# p2c-001.net
KiCad netlist of a schematic drawn in EAGLE
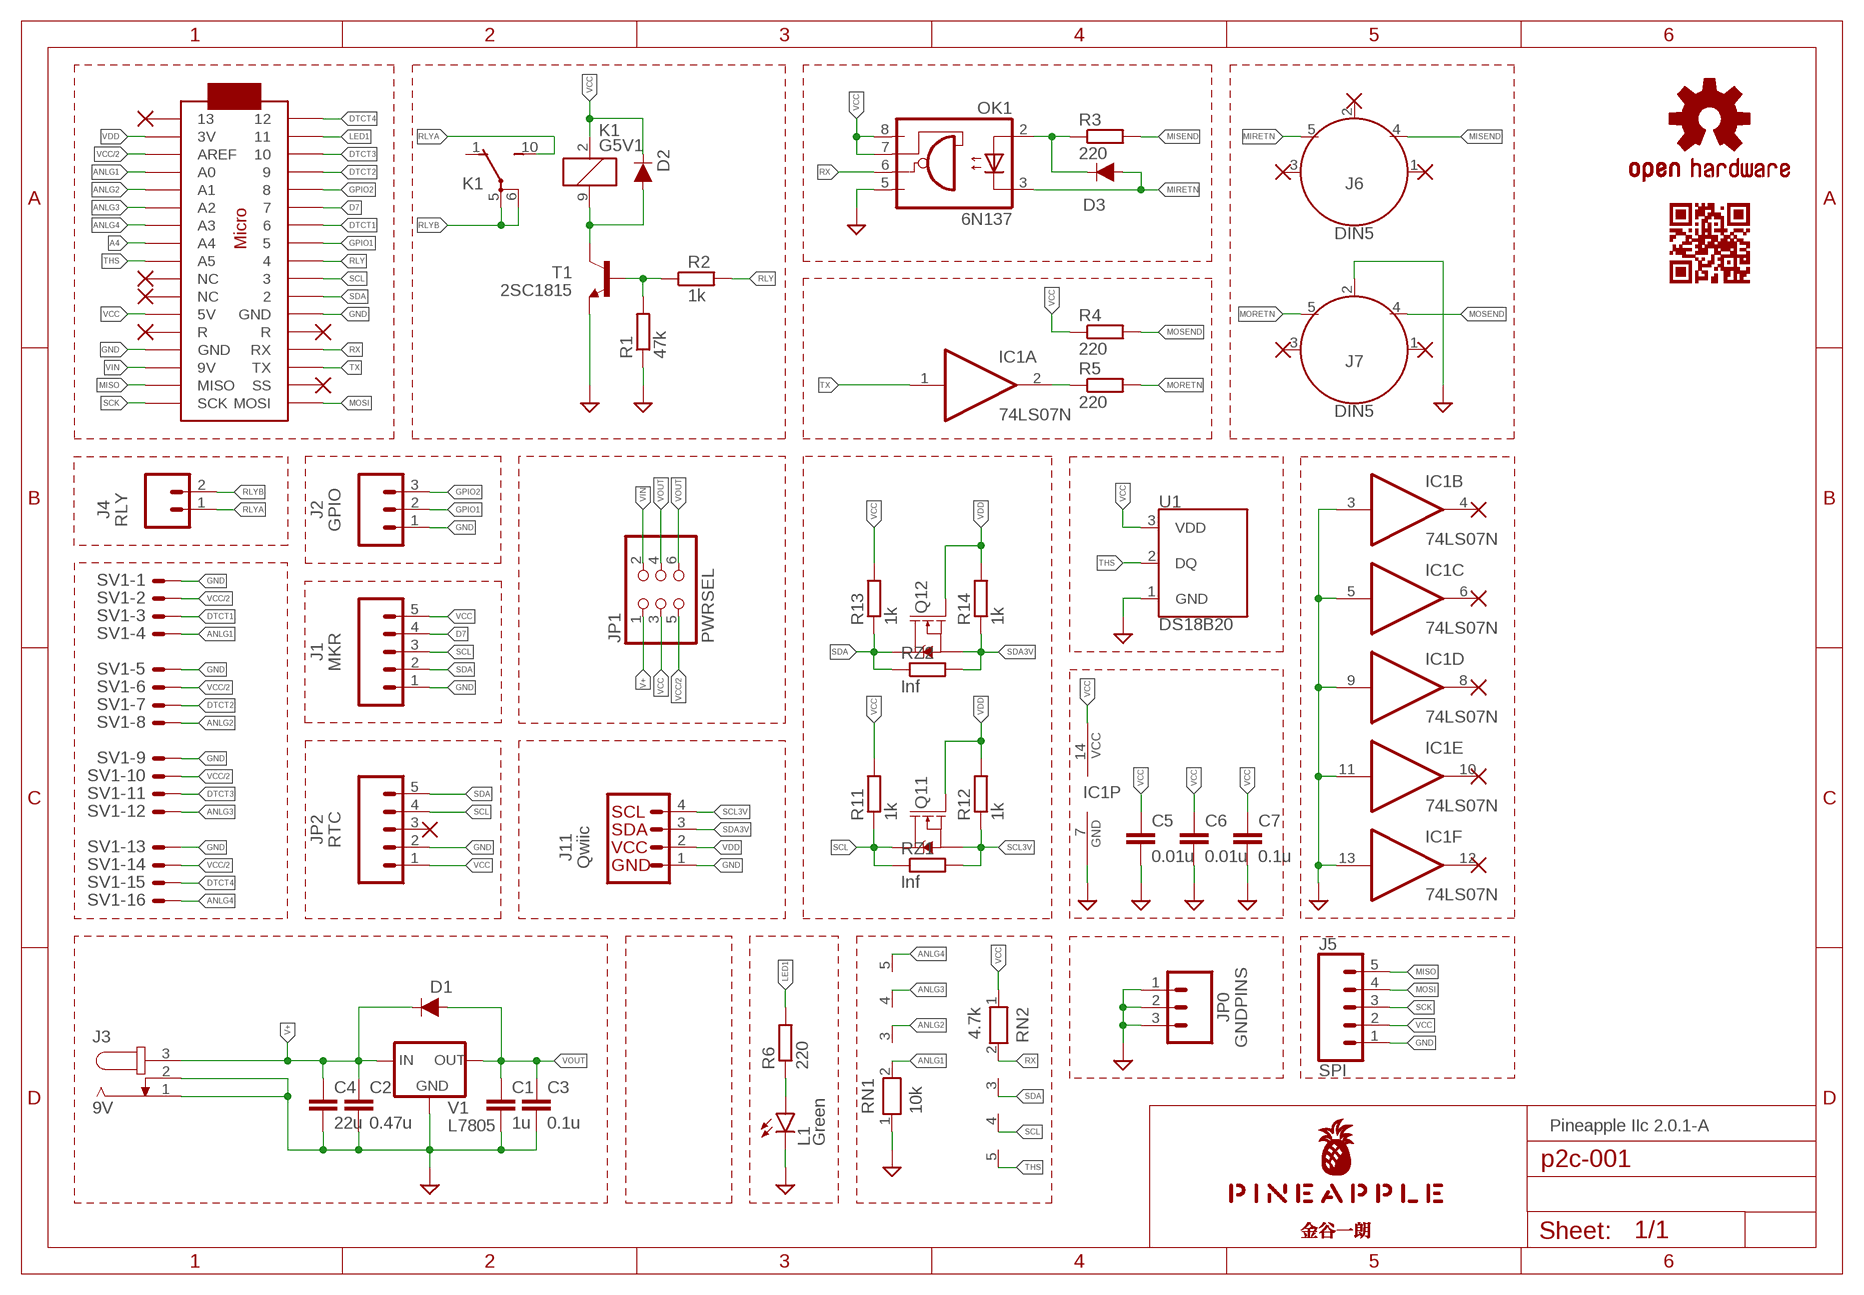
[diagram p0: schematic, sheet 1]

(export (version "E")
  (design (tool "Eeschema 10.0.6"))
  (components
    (comp (ref "C1")
      (value "1u")
      (footprint "eagle-import:C050-024X044")
      (libsource (lib "eagle-import") (part "C-EU050-024X044"))
    )
    (comp (ref "C2")
      (value "0.47u")
      (footprint "eagle-import:C050-024X044")
      (libsource (lib "eagle-import") (part "C-EU050-024X044"))
    )
    (comp (ref "C3")
      (value "0.1u")
      (footprint "eagle-import:C025-024X044")
      (libsource (lib "eagle-import") (part "C-EU025-024X044"))
    )
    (comp (ref "C4")
      (value "22u")
      (footprint "eagle-import:C025-050X050")
      (libsource (lib "eagle-import") (part "C-EU025-050X050"))
    )
    (comp (ref "C5")
      (value "0.01u")
      (footprint "eagle-import:C025-024X044")
      (libsource (lib "eagle-import") (part "resistor_348_C-EU025-024X044"))
    )
    (comp (ref "C6")
      (value "0.01u")
      (footprint "eagle-import:C025-024X044")
      (libsource (lib "eagle-import") (part "resistor_348_C-EU025-024X044"))
    )
    (comp (ref "C7")
      (value "0.1u")
      (footprint "eagle-import:C025-024X044")
      (libsource (lib "eagle-import") (part "C-EU025-024X044"))
    )
    (comp (ref "D1")
      (value "DIODE-1N4148")
      (footprint "eagle-import:DIODE-1N4148")
      (libsource (lib "eagle-import") (part "DIODE-1N4148"))
    )
    (comp (ref "D2")
      (value "DIODE-1N4148")
      (footprint "eagle-import:DIODE-1N4148")
      (libsource (lib "eagle-import") (part "DIODE-1N4148"))
    )
    (comp (ref "D3")
      (value "DIODE-1N4148")
      (footprint "eagle-import:DIODE-1N4148")
      (libsource (lib "eagle-import") (part "DIODE-1N4148"))
    )
    (comp (ref "IC1")
      (value "74LS07N")
      (footprint "eagle-import:DIL14")
      (libsource (lib "eagle-import") (part "7407NLS"))
    )
    (comp (ref "J1")
      (value "MKR")
      (footprint "eagle-import:JST-5-PTH")
      (libsource (lib "eagle-import") (part "CONN_05JST"))
    )
    (comp (ref "J2")
      (value "GPIO")
      (footprint "eagle-import:JST-3-PTH")
      (libsource (lib "eagle-import") (part "CONN_03JST-PTH"))
    )
    (comp (ref "J3")
      (value "9V")
      (footprint "eagle-import:SPC4077")
      (libsource (lib "eagle-import") (part "JACK-PLUG0"))
    )
    (comp (ref "J4")
      (value "RLY")
      (footprint "eagle-import:JST-2-PTH")
      (libsource (lib "eagle-import") (part "CONN_02JST-PTH-2"))
    )
    (comp (ref "J5")
      (value "SPI")
      (footprint "eagle-import:JST-5-PTH-VERT")
      (libsource (lib "eagle-import") (part "CONN_05JST-VERT"))
    )
    (comp (ref "J6")
      (value "DIN5")
      (footprint "eagle-import:DIN5-RA-PTH")
      (libsource (lib "eagle-import") (part "DIN5"))
    )
    (comp (ref "J7")
      (value "DIN5")
      (footprint "eagle-import:DIN5-RA-PTH")
      (libsource (lib "eagle-import") (part "DIN5"))
    )
    (comp (ref "J11")
      (value "Qwiic")
      (footprint "eagle-import:1X04_1MM_RA")
      (libsource (lib "eagle-import") (part "QWIIC_CONNECTORJS-1MM"))
    )
    (comp (ref "JP0")
      (value "GNDPINS")
      (footprint "eagle-import:1X03")
      (libsource (lib "eagle-import") (part "CONN_03"))
    )
    (comp (ref "JP1")
      (value "PWRSEL")
      (footprint "eagle-import:2X03")
      (libsource (lib "eagle-import") (part "PINHD-2X3"))
    )
    (comp (ref "JP2")
      (value "RTC")
      (footprint "eagle-import:1X05")
      (libsource (lib "eagle-import") (part "CONN_05"))
    )
    (comp (ref "K1")
      (value "G5V1")
      (footprint "eagle-import:G5V1")
      (fields (field (name "MPN") "G5V-1-DC24"))
      (libsource (lib "eagle-import") (part "G5V1"))
    )
    (comp (ref "L1")
      (value "Green")
      (footprint "eagle-import:LED3MM")
      (libsource (lib "eagle-import") (part "LED3MM"))
    )
    (comp (ref "LOGO1")
      (value "OSHW-LOGOS-COPPER")
      (footprint "eagle-import:OSHW-LOGO-S_COPPER")
      (libsource (lib "eagle-import") (part "OSHW-LOGOS-COPPER"))
    )
    (comp (ref "OK1")
      (value "6N137")
      (footprint "eagle-import:DIL08")
      (libsource (lib "eagle-import") (part "6N137"))
    )
    (comp (ref "Q11")
      (value "220mA/50V/3.5Ω")
      (footprint "eagle-import:SOT23-3")
      (libsource (lib "eagle-import") (part "MOSFET-NCH-BSS138"))
    )
    (comp (ref "Q12")
      (value "220mA/50V/3.5Ω")
      (footprint "eagle-import:SOT23-3")
      (libsource (lib "eagle-import") (part "MOSFET-NCH-BSS138"))
    )
    (comp (ref "R1")
      (value "47k")
      (footprint "eagle-import:0204_5")
      (libsource (lib "eagle-import") (part "R-EU_0204/5"))
    )
    (comp (ref "R2")
      (value "1k")
      (footprint "eagle-import:0204_5")
      (libsource (lib "eagle-import") (part "R-EU_0204/5"))
    )
    (comp (ref "R3")
      (value "220")
      (footprint "eagle-import:0204_5")
      (libsource (lib "eagle-import") (part "R-EU_0204/5"))
    )
    (comp (ref "R4")
      (value "220")
      (footprint "eagle-import:0204_5")
      (libsource (lib "eagle-import") (part "R-EU_0204/5"))
    )
    (comp (ref "R5")
      (value "220")
      (footprint "eagle-import:0204_5")
      (libsource (lib "eagle-import") (part "R-EU_0204/5"))
    )
    (comp (ref "R6")
      (value "220")
      (footprint "eagle-import:0204_5")
      (libsource (lib "eagle-import") (part "R-EU_0204/5"))
    )
    (comp (ref "R11")
      (value "1k")
      (footprint "eagle-import:R2012")
      (libsource (lib "eagle-import") (part "R-EU_R2012"))
    )
    (comp (ref "R12")
      (value "1k")
      (footprint "eagle-import:R2012")
      (libsource (lib "eagle-import") (part "R-EU_R2012"))
    )
    (comp (ref "R13")
      (value "1k")
      (footprint "eagle-import:R2012")
      (libsource (lib "eagle-import") (part "R-EU_R2012"))
    )
    (comp (ref "R14")
      (value "1k")
      (footprint "eagle-import:R2012")
      (libsource (lib "eagle-import") (part "R-EU_R2012"))
    )
    (comp (ref "RN1")
      (value "10k")
      (footprint "eagle-import:RN-5")
      (libsource (lib "eagle-import") (part "RN04"))
    )
    (comp (ref "RN2")
      (value "4.7k")
      (footprint "eagle-import:RN-5")
      (libsource (lib "eagle-import") (part "RN04"))
    )
    (comp (ref "RZ1")
      (value "Inf")
      (footprint "eagle-import:R2012")
      (libsource (lib "eagle-import") (part "R-EU_R2012"))
    )
    (comp (ref "RZ2")
      (value "Inf")
      (footprint "eagle-import:R2012")
      (libsource (lib "eagle-import") (part "R-EU_R2012"))
    )
    (comp (ref "SV1")
      (value "ML16LE")
      (footprint "eagle-import:ML16L")
      (libsource (lib "eagle-import") (part "ML16LE"))
    )
    (comp (ref "T1")
      (value "2SC1815")
      (footprint "eagle-import:TO92-ECB")
      (libsource (lib "eagle-import") (part "2SC1815"))
    )
    (comp (ref "U$1")
      (value "PINEAPPLE450_SILK")
      (footprint "eagle-import:PINEAPPLE450_SILK")
      (libsource (lib "eagle-import") (part "PINEAPPLE450_SILK"))
    )
    (comp (ref "U$2")
      (value "ARDUINOMICRO")
      (footprint "eagle-import:ARDUINOMICRO")
      (libsource (lib "eagle-import") (part "ARDUINOMICRO"))
    )
    (comp (ref "U$3")
      (value "KANAYA768_SILK")
      (footprint "eagle-import:KANAYA768_SILK")
      (libsource (lib "eagle-import") (part "KANAYA768_SILK"))
    )
    (comp (ref "U$4")
      (value "CARDQRCODE450_SILK")
      (footprint "eagle-import:CARDQRCODE450_SILK")
      (libsource (lib "eagle-import") (part "CARDQRCODE450_SILK"))
    )
    (comp (ref "U1")
      (value "DS18B20")
      (footprint "eagle-import:TO-92-AMMO")
      (libsource (lib "eagle-import") (part "DS18B20"))
    )
    (comp (ref "V1")
      (value "L7805")
      (footprint "eagle-import:78XXS")
      (libsource (lib "eagle-import") (part "78XXS"))
    )
  )
  (nets
    (net (code "1") (name "A4") (class "Default")
      (node (ref "U$2") (pin "P$27") (pinfunction "A4_P$27") (pintype "bidirectional"))
    )
    (net (code "2") (name "ANLG1") (class "Default")
      (node (ref "RN1") (pin "2") (pinfunction "2_2") (pintype "passive"))
      (node (ref "SV1") (pin "4") (pinfunction "S_4") (pintype "passive"))
      (node (ref "U$2") (pin "P$31") (pinfunction "A0_P$31") (pintype "bidirectional"))
    )
    (net (code "3") (name "ANLG2") (class "Default")
      (node (ref "RN1") (pin "3") (pinfunction "3_3") (pintype "passive"))
      (node (ref "SV1") (pin "8") (pinfunction "S_8") (pintype "passive"))
      (node (ref "U$2") (pin "P$30") (pinfunction "A1_P$30") (pintype "bidirectional"))
    )
    (net (code "4") (name "ANLG3") (class "Default")
      (node (ref "RN1") (pin "4") (pinfunction "4_4") (pintype "passive"))
      (node (ref "SV1") (pin "12") (pinfunction "S_12") (pintype "passive"))
      (node (ref "U$2") (pin "P$29") (pinfunction "A2_P$29") (pintype "bidirectional"))
    )
    (net (code "5") (name "ANLG4") (class "Default")
      (node (ref "RN1") (pin "5") (pinfunction "5_5") (pintype "passive"))
      (node (ref "SV1") (pin "16") (pinfunction "S_16") (pintype "passive"))
      (node (ref "U$2") (pin "P$28") (pinfunction "A3_P$28") (pintype "bidirectional"))
    )
    (net (code "6") (name "D7") (class "Default")
      (node (ref "J1") (pin "4") (pinfunction "4_4") (pintype "passive"))
      (node (ref "U$2") (pin "P$6") (pinfunction "7_P$6") (pintype "bidirectional"))
    )
    (net (code "7") (name "DTCT1") (class "Default")
      (node (ref "SV1") (pin "3") (pinfunction "S_3") (pintype "passive"))
      (node (ref "U$2") (pin "P$7") (pinfunction "6_P$7") (pintype "bidirectional"))
    )
    (net (code "8") (name "DTCT2") (class "Default")
      (node (ref "SV1") (pin "7") (pinfunction "S_7") (pintype "passive"))
      (node (ref "U$2") (pin "P$4") (pinfunction "9_P$4") (pintype "bidirectional"))
    )
    (net (code "9") (name "DTCT3") (class "Default")
      (node (ref "SV1") (pin "11") (pinfunction "S_11") (pintype "passive"))
      (node (ref "U$2") (pin "P$3") (pinfunction "10_P$3") (pintype "bidirectional"))
    )
    (net (code "10") (name "DTCT4") (class "Default")
      (node (ref "SV1") (pin "15") (pinfunction "S_15") (pintype "passive"))
      (node (ref "U$2") (pin "P$1") (pinfunction "12_P$1") (pintype "bidirectional"))
    )
    (net (code "11") (name "GND") (class "Default")
      (node (ref "C1") (pin "2") (pinfunction "2_2") (pintype "passive"))
      (node (ref "C2") (pin "2") (pinfunction "2_2") (pintype "passive"))
      (node (ref "C3") (pin "2") (pinfunction "2_2") (pintype "passive"))
      (node (ref "C4") (pin "2") (pinfunction "2_2") (pintype "passive"))
      (node (ref "C5") (pin "2") (pinfunction "2_2") (pintype "passive"))
      (node (ref "C6") (pin "2") (pinfunction "2_2") (pintype "passive"))
      (node (ref "C7") (pin "2") (pinfunction "2_2") (pintype "passive"))
      (node (ref "IC1") (pin "11") (pinfunction "I_11") (pintype "input"))
      (node (ref "IC1") (pin "13") (pinfunction "I_13") (pintype "input"))
      (node (ref "IC1") (pin "3") (pinfunction "I_3") (pintype "input"))
      (node (ref "IC1") (pin "5") (pinfunction "I_5") (pintype "input"))
      (node (ref "IC1") (pin "7") (pinfunction "GND_7") (pintype "power_in"))
      (node (ref "IC1") (pin "9") (pinfunction "I_9") (pintype "input"))
      (node (ref "J1") (pin "1") (pinfunction "1_1") (pintype "passive"))
      (node (ref "J11") (pin "1") (pinfunction "GND_1") (pintype "power_in"))
      (node (ref "J2") (pin "1") (pinfunction "1_1") (pintype "passive"))
      (node (ref "J3") (pin "1") (pinfunction "1_1") (pintype "passive"))
      (node (ref "J3") (pin "2") (pinfunction "2_2") (pintype "passive"))
      (node (ref "J5") (pin "1") (pinfunction "1_1") (pintype "passive"))
      (node (ref "J7") (pin "2") (pinfunction "2_2") (pintype "bidirectional"))
      (node (ref "JP0") (pin "1") (pinfunction "1_1") (pintype "passive"))
      (node (ref "JP0") (pin "2") (pinfunction "2_2") (pintype "passive"))
      (node (ref "JP0") (pin "3") (pinfunction "3_3") (pintype "passive"))
      (node (ref "JP2") (pin "2") (pinfunction "2_2") (pintype "passive"))
      (node (ref "L1") (pin "K") (pinfunction "C_K") (pintype "passive"))
      (node (ref "OK1") (pin "5") (pinfunction "GND_5") (pintype "passive"))
      (node (ref "R1") (pin "1") (pinfunction "1_1") (pintype "passive"))
      (node (ref "RN1") (pin "1") (pinfunction "1_1") (pintype "passive"))
      (node (ref "SV1") (pin "1") (pinfunction "S_1") (pintype "passive"))
      (node (ref "SV1") (pin "13") (pinfunction "S_13") (pintype "passive"))
      (node (ref "SV1") (pin "5") (pinfunction "S_5") (pintype "passive"))
      (node (ref "SV1") (pin "9") (pinfunction "S_9") (pintype "passive"))
      (node (ref "T1") (pin "E") (pinfunction "E_E") (pintype "passive"))
      (node (ref "U$2") (pin "P$12") (pinfunction "GND_P$12") (pintype "bidirectional"))
      (node (ref "U$2") (pin "P$21") (pinfunction "GND_P$21") (pintype "bidirectional"))
      (node (ref "U1") (pin "1") (pinfunction "GND_1") (pintype "power_in"))
      (node (ref "V1") (pin "GND") (pinfunction "GND_GND") (pintype "input"))
    )
    (net (code "12") (name "GPIO1") (class "Default")
      (node (ref "J2") (pin "2") (pinfunction "2_2") (pintype "passive"))
      (node (ref "U$2") (pin "P$8") (pinfunction "5_P$8") (pintype "bidirectional"))
    )
    (net (code "13") (name "GPIO2") (class "Default")
      (node (ref "J2") (pin "3") (pinfunction "3_3") (pintype "passive"))
      (node (ref "U$2") (pin "P$5") (pinfunction "8_P$5") (pintype "bidirectional"))
    )
    (net (code "14") (name "LED1") (class "Default")
      (node (ref "R6") (pin "2") (pinfunction "2_2") (pintype "passive"))
      (node (ref "U$2") (pin "P$2") (pinfunction "11_P$2") (pintype "bidirectional"))
    )
    (net (code "15") (name "MIRETN") (class "Default")
      (node (ref "D3") (pin "A") (pinfunction "A_A") (pintype "passive"))
      (node (ref "J6") (pin "5") (pinfunction "5_5") (pintype "bidirectional"))
      (node (ref "OK1") (pin "3") (pinfunction "C_3") (pintype "passive"))
    )
    (net (code "16") (name "MISEND") (class "Default")
      (node (ref "J6") (pin "4") (pinfunction "4_4") (pintype "bidirectional"))
      (node (ref "R3") (pin "2") (pinfunction "2_2") (pintype "passive"))
    )
    (net (code "17") (name "MISO") (class "Default")
      (node (ref "J5") (pin "5") (pinfunction "5_5") (pintype "passive"))
      (node (ref "U$2") (pin "P$19") (pinfunction "MISO_P$19") (pintype "bidirectional"))
    )
    (net (code "18") (name "MORETN") (class "Default")
      (node (ref "J7") (pin "5") (pinfunction "5_5") (pintype "bidirectional"))
      (node (ref "R5") (pin "2") (pinfunction "2_2") (pintype "passive"))
    )
    (net (code "19") (name "MOSEND") (class "Default")
      (node (ref "J7") (pin "4") (pinfunction "4_4") (pintype "bidirectional"))
      (node (ref "R4") (pin "2") (pinfunction "2_2") (pintype "passive"))
    )
    (net (code "20") (name "MOSI") (class "Default")
      (node (ref "J5") (pin "4") (pinfunction "4_4") (pintype "passive"))
      (node (ref "U$2") (pin "P$17") (pinfunction "MOSI_P$17") (pintype "bidirectional"))
    )
    (net (code "21") (name "Net-(IC1A-O)") (class "Default")
      (node (ref "IC1") (pin "2") (pinfunction "O_2") (pintype "open_collector"))
      (node (ref "R5") (pin "1") (pinfunction "1_1") (pintype "passive"))
    )
    (net (code "22") (name "Net-(K1A-2)") (class "Default")
      (node (ref "D2") (pin "A") (pinfunction "A_A") (pintype "passive"))
      (node (ref "K1") (pin "9") (pinfunction "2_9") (pintype "passive"))
      (node (ref "T1") (pin "C") (pinfunction "C_C") (pintype "passive"))
    )
    (net (code "23") (name "Net-(L1-PadA)") (class "Default")
      (node (ref "L1") (pin "A") (pinfunction "A_A") (pintype "passive"))
      (node (ref "R6") (pin "1") (pinfunction "1_1") (pintype "passive"))
    )
    (net (code "24") (name "Net-(OK1-A)") (class "Default")
      (node (ref "D3") (pin "C") (pinfunction "C_C") (pintype "passive"))
      (node (ref "OK1") (pin "2") (pinfunction "A_2") (pintype "passive"))
      (node (ref "R3") (pin "1") (pinfunction "1_1") (pintype "passive"))
    )
    (net (code "25") (name "Net-(R1-Pad2)") (class "Default")
      (node (ref "R1") (pin "2") (pinfunction "2_2") (pintype "passive"))
      (node (ref "R2") (pin "1") (pinfunction "1_1") (pintype "passive"))
      (node (ref "T1") (pin "B") (pinfunction "B_B") (pintype "passive"))
    )
    (net (code "26") (name "RLY") (class "Default")
      (node (ref "R2") (pin "2") (pinfunction "2_2") (pintype "passive"))
      (node (ref "U$2") (pin "P$9") (pinfunction "4_P$9") (pintype "bidirectional"))
    )
    (net (code "27") (name "RLYA") (class "Default")
      (node (ref "J4") (pin "1") (pinfunction "1_1") (pintype "passive"))
      (node (ref "K1") (pin "10") (pinfunction "S_10") (pintype "passive"))
    )
    (net (code "28") (name "RLYB") (class "Default")
      (node (ref "J4") (pin "2") (pinfunction "2_2") (pintype "passive"))
      (node (ref "K1") (pin "5") (pinfunction "P_5") (pintype "passive"))
      (node (ref "K1") (pin "6") (pinfunction "P_6") (pintype "passive"))
    )
    (net (code "29") (name "RX") (class "Default")
      (node (ref "OK1") (pin "6") (pinfunction "VO_6") (pintype "passive"))
      (node (ref "RN2") (pin "2") (pinfunction "2_2") (pintype "passive"))
      (node (ref "U$2") (pin "P$14") (pinfunction "RX_P$14") (pintype "bidirectional"))
    )
    (net (code "30") (name "SCK") (class "Default")
      (node (ref "J5") (pin "3") (pinfunction "3_3") (pintype "passive"))
      (node (ref "U$2") (pin "P$18") (pinfunction "SCK_P$18") (pintype "bidirectional"))
    )
    (net (code "31") (name "SCL") (class "Default")
      (node (ref "J1") (pin "3") (pinfunction "3_3") (pintype "passive"))
      (node (ref "JP2") (pin "4") (pinfunction "4_4") (pintype "passive"))
      (node (ref "Q11") (pin "3") (pinfunction "D_3") (pintype "bidirectional"))
      (node (ref "R11") (pin "1") (pinfunction "1_1") (pintype "passive"))
      (node (ref "RN2") (pin "4") (pinfunction "4_4") (pintype "passive"))
      (node (ref "RZ1") (pin "1") (pinfunction "1_1") (pintype "passive"))
      (node (ref "U$2") (pin "P$10") (pinfunction "3_P$10") (pintype "bidirectional"))
    )
    (net (code "32") (name "SCL3V") (class "Default")
      (node (ref "J11") (pin "4") (pinfunction "SCL_4") (pintype "passive"))
      (node (ref "Q11") (pin "2") (pinfunction "S_2") (pintype "bidirectional"))
      (node (ref "R12") (pin "1") (pinfunction "1_1") (pintype "passive"))
      (node (ref "RZ1") (pin "2") (pinfunction "2_2") (pintype "passive"))
    )
    (net (code "33") (name "SDA") (class "Default")
      (node (ref "J1") (pin "2") (pinfunction "2_2") (pintype "passive"))
      (node (ref "JP2") (pin "5") (pinfunction "5_5") (pintype "passive"))
      (node (ref "Q12") (pin "3") (pinfunction "D_3") (pintype "bidirectional"))
      (node (ref "R13") (pin "1") (pinfunction "1_1") (pintype "passive"))
      (node (ref "RN2") (pin "3") (pinfunction "3_3") (pintype "passive"))
      (node (ref "RZ2") (pin "1") (pinfunction "1_1") (pintype "passive"))
      (node (ref "U$2") (pin "P$11") (pinfunction "2_P$11") (pintype "bidirectional"))
    )
    (net (code "34") (name "SDA3V") (class "Default")
      (node (ref "J11") (pin "3") (pinfunction "SDA_3") (pintype "passive"))
      (node (ref "Q12") (pin "2") (pinfunction "S_2") (pintype "bidirectional"))
      (node (ref "R14") (pin "1") (pinfunction "1_1") (pintype "passive"))
      (node (ref "RZ2") (pin "2") (pinfunction "2_2") (pintype "passive"))
    )
    (net (code "35") (name "THS") (class "Default")
      (node (ref "RN2") (pin "5") (pinfunction "5_5") (pintype "passive"))
      (node (ref "U$2") (pin "P$26") (pinfunction "A5_P$26") (pintype "bidirectional"))
      (node (ref "U1") (pin "2") (pinfunction "DQ_2") (pintype "bidirectional"))
    )
    (net (code "36") (name "TX") (class "Default")
      (node (ref "IC1") (pin "1") (pinfunction "I_1") (pintype "input"))
      (node (ref "U$2") (pin "P$15") (pinfunction "TX_P$15") (pintype "bidirectional"))
    )
    (net (code "37") (name "V+") (class "Default")
      (node (ref "C2") (pin "1") (pinfunction "1_1") (pintype "passive"))
      (node (ref "C4") (pin "1") (pinfunction "1_1") (pintype "passive"))
      (node (ref "D1") (pin "C") (pinfunction "C_C") (pintype "passive"))
      (node (ref "J3") (pin "3") (pinfunction "3_3") (pintype "passive"))
      (node (ref "JP1") (pin "1") (pinfunction "1_1") (pintype "passive"))
      (node (ref "V1") (pin "IN") (pinfunction "IN_IN") (pintype "input"))
    )
    (net (code "38") (name "VCC") (class "Default")
      (node (ref "C5") (pin "1") (pinfunction "1_1") (pintype "passive"))
      (node (ref "C6") (pin "1") (pinfunction "1_1") (pintype "passive"))
      (node (ref "C7") (pin "1") (pinfunction "1_1") (pintype "passive"))
      (node (ref "D2") (pin "C") (pinfunction "C_C") (pintype "passive"))
      (node (ref "IC1") (pin "14") (pinfunction "VCC_14") (pintype "power_in"))
      (node (ref "J1") (pin "5") (pinfunction "5_5") (pintype "passive"))
      (node (ref "J5") (pin "2") (pinfunction "2_2") (pintype "passive"))
      (node (ref "JP1") (pin "3") (pinfunction "3_3") (pintype "passive"))
      (node (ref "JP2") (pin "1") (pinfunction "1_1") (pintype "passive"))
      (node (ref "K1") (pin "2") (pinfunction "1_2") (pintype "passive"))
      (node (ref "OK1") (pin "7") (pinfunction "VE_7") (pintype "passive"))
      (node (ref "OK1") (pin "8") (pinfunction "VCC_8") (pintype "passive"))
      (node (ref "R11") (pin "2") (pinfunction "2_2") (pintype "passive"))
      (node (ref "R13") (pin "2") (pinfunction "2_2") (pintype "passive"))
      (node (ref "R4") (pin "1") (pinfunction "1_1") (pintype "passive"))
      (node (ref "RN2") (pin "1") (pinfunction "1_1") (pintype "passive"))
      (node (ref "U$2") (pin "P$23") (pinfunction "5V_P$23") (pintype "bidirectional"))
      (node (ref "U1") (pin "3") (pinfunction "VDD_3") (pintype "power_in"))
    )
    (net (code "39") (name "VCC{slash}2") (class "Default")
      (node (ref "JP1") (pin "5") (pinfunction "5_5") (pintype "passive"))
      (node (ref "SV1") (pin "10") (pinfunction "S_10") (pintype "passive"))
      (node (ref "SV1") (pin "14") (pinfunction "S_14") (pintype "passive"))
      (node (ref "SV1") (pin "2") (pinfunction "S_2") (pintype "passive"))
      (node (ref "SV1") (pin "6") (pinfunction "S_6") (pintype "passive"))
      (node (ref "U$2") (pin "P$32") (pinfunction "AREF_P$32") (pintype "bidirectional"))
    )
    (net (code "40") (name "VDD") (class "Default")
      (node (ref "J11") (pin "2") (pinfunction "VCC_2") (pintype "power_in"))
      (node (ref "Q11") (pin "1") (pinfunction "G_1") (pintype "bidirectional"))
      (node (ref "Q12") (pin "1") (pinfunction "G_1") (pintype "bidirectional"))
      (node (ref "R12") (pin "2") (pinfunction "2_2") (pintype "passive"))
      (node (ref "R14") (pin "2") (pinfunction "2_2") (pintype "passive"))
      (node (ref "U$2") (pin "P$33") (pinfunction "3V_P$33") (pintype "bidirectional"))
    )
    (net (code "41") (name "VIN") (class "Default")
      (node (ref "JP1") (pin "2") (pinfunction "2_2") (pintype "passive"))
      (node (ref "U$2") (pin "P$20") (pinfunction "9V_P$20") (pintype "bidirectional"))
    )
    (net (code "42") (name "VOUT") (class "Default")
      (node (ref "C1") (pin "1") (pinfunction "1_1") (pintype "passive"))
      (node (ref "C3") (pin "1") (pinfunction "1_1") (pintype "passive"))
      (node (ref "D1") (pin "A") (pinfunction "A_A") (pintype "passive"))
      (node (ref "JP1") (pin "4") (pinfunction "4_4") (pintype "passive"))
      (node (ref "JP1") (pin "6") (pinfunction "6_6") (pintype "passive"))
      (node (ref "V1") (pin "OUT") (pinfunction "OUT_OUT") (pintype "passive"))
    )
    (net (code "43") (name "unconnected-(IC1B-O-Pad4)") (class "Default")
      (node (ref "IC1") (pin "4") (pinfunction "O_4") (pintype "open_collector"))
    )
    (net (code "44") (name "unconnected-(IC1C-O-Pad6)") (class "Default")
      (node (ref "IC1") (pin "6") (pinfunction "O_6") (pintype "open_collector"))
    )
    (net (code "45") (name "unconnected-(IC1D-O-Pad8)") (class "Default")
      (node (ref "IC1") (pin "8") (pinfunction "O_8") (pintype "open_collector"))
    )
    (net (code "46") (name "unconnected-(IC1E-O-Pad10)") (class "Default")
      (node (ref "IC1") (pin "10") (pinfunction "O_10") (pintype "open_collector"))
    )
    (net (code "47") (name "unconnected-(IC1F-O-Pad12)") (class "Default")
      (node (ref "IC1") (pin "12") (pinfunction "O_12") (pintype "open_collector"))
    )
    (net (code "48") (name "unconnected-(J6-Pad1)") (class "Default")
      (node (ref "J6") (pin "1") (pinfunction "1_1") (pintype "bidirectional"))
    )
    (net (code "49") (name "unconnected-(J6-Pad2)") (class "Default")
      (node (ref "J6") (pin "2") (pinfunction "2_2") (pintype "bidirectional"))
    )
    (net (code "50") (name "unconnected-(J6-Pad3)") (class "Default")
      (node (ref "J6") (pin "3") (pinfunction "3_3") (pintype "bidirectional"))
    )
    (net (code "51") (name "unconnected-(J7-Pad1)") (class "Default")
      (node (ref "J7") (pin "1") (pinfunction "1_1") (pintype "bidirectional"))
    )
    (net (code "52") (name "unconnected-(J7-Pad3)") (class "Default")
      (node (ref "J7") (pin "3") (pinfunction "3_3") (pintype "bidirectional"))
    )
    (net (code "53") (name "unconnected-(JP2-Pad3)") (class "Default")
      (node (ref "JP2") (pin "3") (pinfunction "3_3") (pintype "passive"))
    )
    (net (code "54") (name "unconnected-(K1B-O-Pad1)") (class "Default")
      (node (ref "K1") (pin "1") (pinfunction "O_1") (pintype "passive"))
    )
    (net (code "55") (name "unconnected-(U$2-13-PadP$34)") (class "Default")
      (node (ref "U$2") (pin "P$34") (pinfunction "13_P$34") (pintype "bidirectional"))
    )
    (net (code "56") (name "unconnected-(U$2-NC-PadP$24)") (class "Default")
      (node (ref "U$2") (pin "P$24") (pinfunction "NC_P$24") (pintype "bidirectional"))
    )
    (net (code "57") (name "unconnected-(U$2-NC-PadP$25)") (class "Default")
      (node (ref "U$2") (pin "P$25") (pinfunction "NC_P$25") (pintype "bidirectional"))
    )
    (net (code "58") (name "unconnected-(U$2-R-PadP$13)") (class "Default")
      (node (ref "U$2") (pin "P$13") (pinfunction "R_P$13") (pintype "bidirectional"))
    )
    (net (code "59") (name "unconnected-(U$2-R-PadP$22)") (class "Default")
      (node (ref "U$2") (pin "P$22") (pinfunction "R_P$22") (pintype "bidirectional"))
    )
    (net (code "60") (name "unconnected-(U$2-SS-PadP$16)") (class "Default")
      (node (ref "U$2") (pin "P$16") (pinfunction "SS_P$16") (pintype "bidirectional"))
    )
  )
)
